# 24LedConnector_1_1.net
KiCad netlist of a schematic drawn in EAGLE
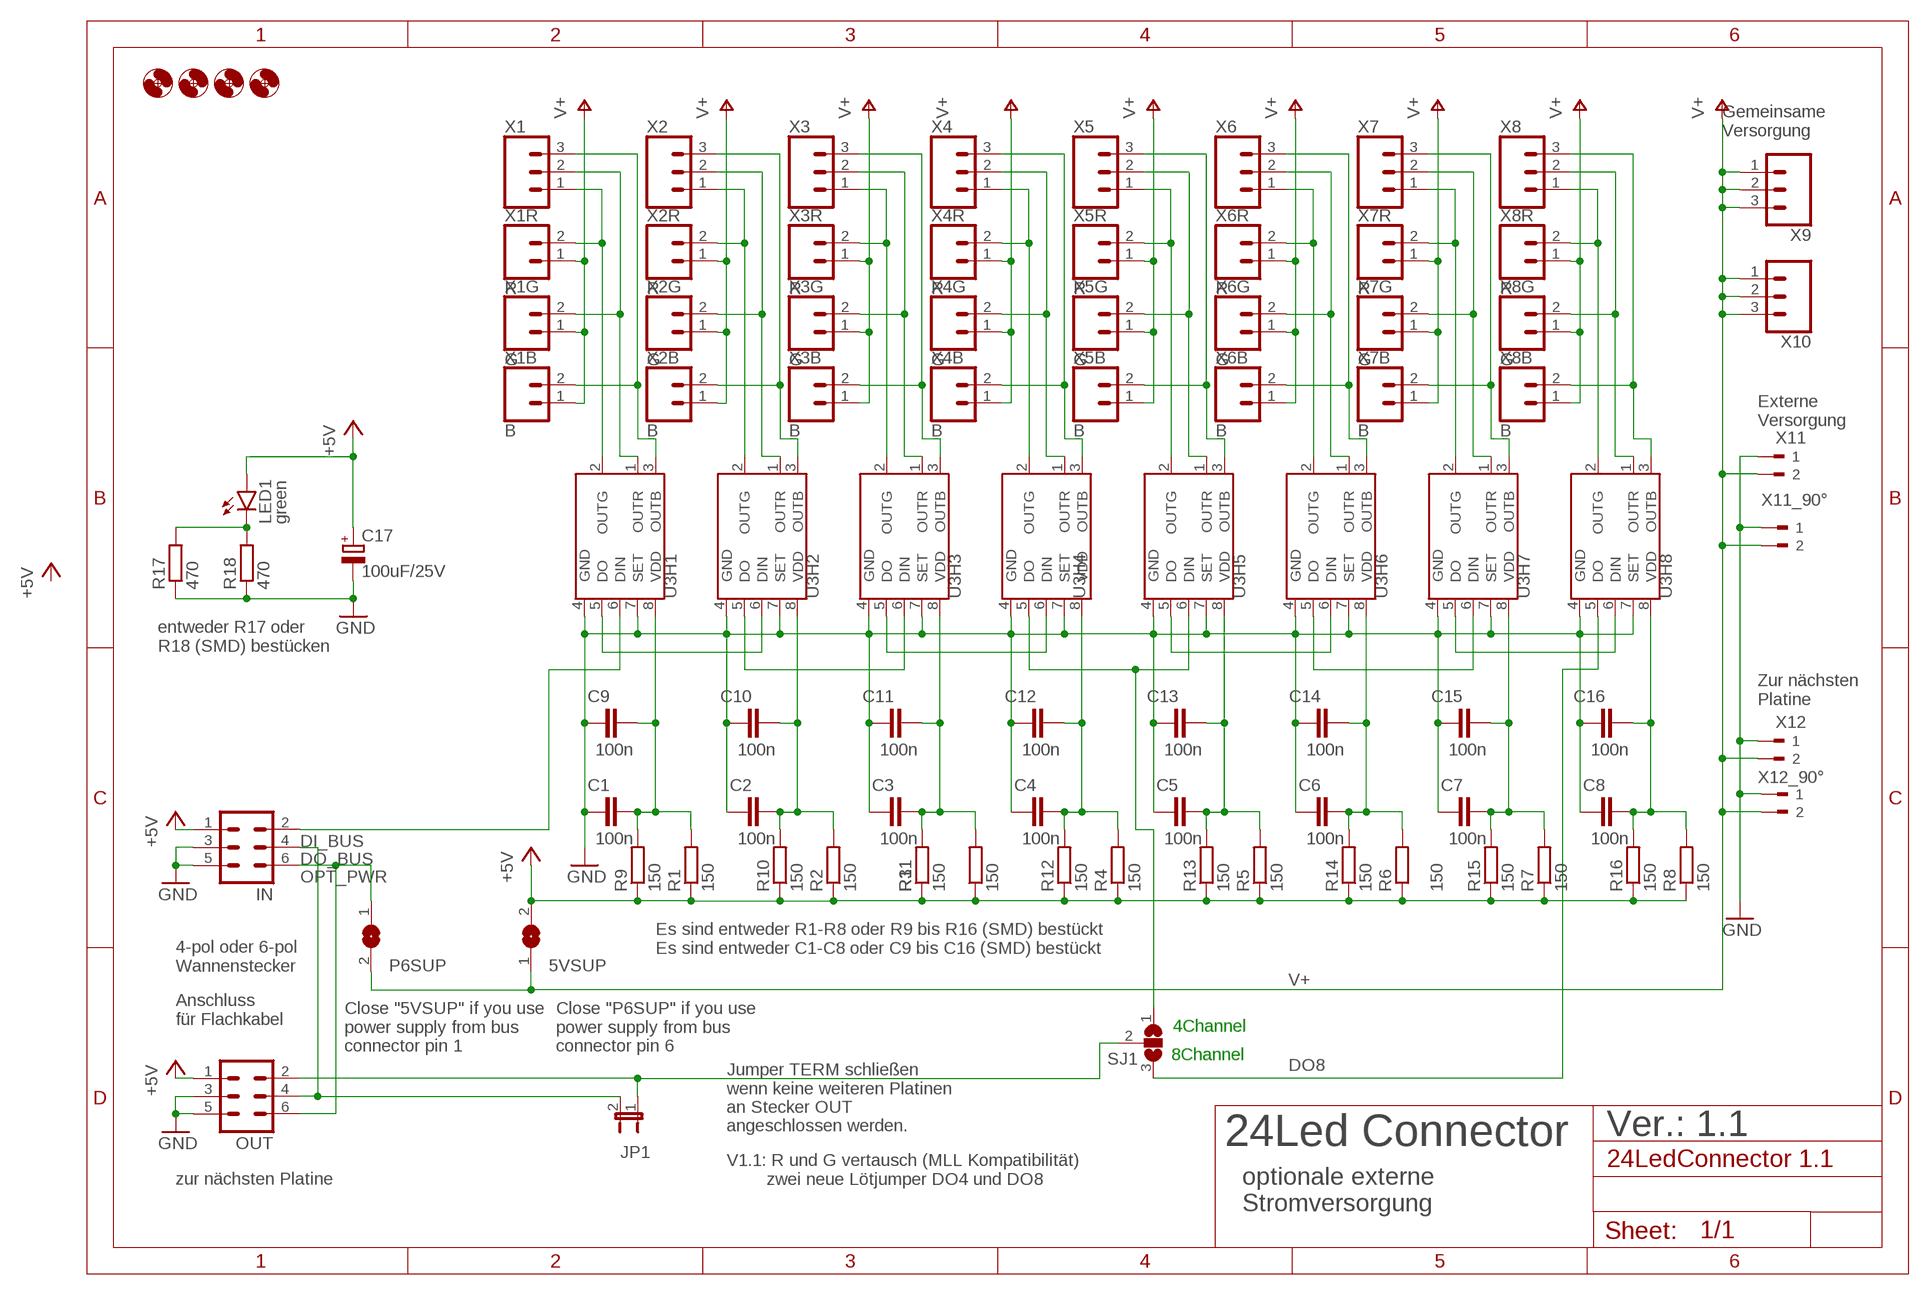
[diagram p0: schematic, sheet 1]

(export (version "E")
  (design (tool "Eeschema 10.0.6"))
  (components
    (comp (ref "5VSUP")
      (value "SJ")
      (footprint "eagle-import:SJ")
      (libsource (lib "eagle-import") (part "SJ"))
    )
    (comp (ref "C1")
      (value "100n")
      (footprint "eagle-import:C025-024X044")
      (libsource (lib "eagle-import") (part "C-EU025-024X044"))
    )
    (comp (ref "C2")
      (value "100n")
      (footprint "eagle-import:C025-024X044")
      (libsource (lib "eagle-import") (part "C-EU025-024X044"))
    )
    (comp (ref "C3")
      (value "100n")
      (footprint "eagle-import:C025-024X044")
      (libsource (lib "eagle-import") (part "C-EU025-024X044"))
    )
    (comp (ref "C4")
      (value "100n")
      (footprint "eagle-import:C025-024X044")
      (libsource (lib "eagle-import") (part "C-EU025-024X044"))
    )
    (comp (ref "C5")
      (value "100n")
      (footprint "eagle-import:C025-024X044")
      (libsource (lib "eagle-import") (part "C-EU025-024X044"))
    )
    (comp (ref "C6")
      (value "100n")
      (footprint "eagle-import:C025-024X044")
      (libsource (lib "eagle-import") (part "C-EU025-024X044"))
    )
    (comp (ref "C7")
      (value "100n")
      (footprint "eagle-import:C025-024X044")
      (libsource (lib "eagle-import") (part "C-EU025-024X044"))
    )
    (comp (ref "C8")
      (value "100n")
      (footprint "eagle-import:C025-024X044")
      (libsource (lib "eagle-import") (part "C-EU025-024X044"))
    )
    (comp (ref "C9")
      (value "100n")
      (footprint "eagle-import:C0805")
      (libsource (lib "eagle-import") (part "C-EUC0805"))
    )
    (comp (ref "C10")
      (value "100n")
      (footprint "eagle-import:C0805")
      (libsource (lib "eagle-import") (part "C-EUC0805"))
    )
    (comp (ref "C11")
      (value "100n")
      (footprint "eagle-import:C0805")
      (libsource (lib "eagle-import") (part "C-EUC0805"))
    )
    (comp (ref "C12")
      (value "100n")
      (footprint "eagle-import:C0805")
      (libsource (lib "eagle-import") (part "C-EUC0805"))
    )
    (comp (ref "C13")
      (value "100n")
      (footprint "eagle-import:C0805")
      (libsource (lib "eagle-import") (part "C-EUC0805"))
    )
    (comp (ref "C14")
      (value "100n")
      (footprint "eagle-import:C0805")
      (libsource (lib "eagle-import") (part "C-EUC0805"))
    )
    (comp (ref "C15")
      (value "100n")
      (footprint "eagle-import:C0805")
      (libsource (lib "eagle-import") (part "C-EUC0805"))
    )
    (comp (ref "C16")
      (value "100n")
      (footprint "eagle-import:C0805")
      (libsource (lib "eagle-import") (part "C-EUC0805"))
    )
    (comp (ref "C17")
      (value "100uF/25V")
      (footprint "eagle-import:E3,5-8")
      (libsource (lib "eagle-import") (part "CPOL-EUE3.5-8"))
    )
    (comp (ref "H1")
      (value "MOUNT-HOLE2.0")
      (footprint "eagle-import:2,0")
      (libsource (lib "eagle-import") (part "MOUNT-HOLE2.0"))
    )
    (comp (ref "H2")
      (value "MOUNT-HOLE2.0")
      (footprint "eagle-import:2,0")
      (libsource (lib "eagle-import") (part "MOUNT-HOLE2.0"))
    )
    (comp (ref "H3")
      (value "MOUNT-HOLE2.0")
      (footprint "eagle-import:2,0")
      (libsource (lib "eagle-import") (part "MOUNT-HOLE2.0"))
    )
    (comp (ref "H4")
      (value "MOUNT-HOLE2.0")
      (footprint "eagle-import:2,0")
      (libsource (lib "eagle-import") (part "MOUNT-HOLE2.0"))
    )
    (comp (ref "IN")
      (value "ML6")
      (footprint "eagle-import:ML6")
      (libsource (lib "eagle-import") (part "ML6"))
    )
    (comp (ref "JP1")
      (value "JP1E")
      (footprint "eagle-import:JP1")
      (libsource (lib "eagle-import") (part "JP1E"))
    )
    (comp (ref "LED1")
      (value "green")
      (footprint "eagle-import:LED3MM")
      (libsource (lib "eagle-import") (part "LED3MM"))
    )
    (comp (ref "OUT")
      (value "ML6")
      (footprint "eagle-import:ML6")
      (libsource (lib "eagle-import") (part "ML6"))
    )
    (comp (ref "P6SUP")
      (value "SJ")
      (footprint "eagle-import:SJ")
      (libsource (lib "eagle-import") (part "SJ"))
    )
    (comp (ref "R1")
      (value "150")
      (footprint "eagle-import:0204V")
      (libsource (lib "eagle-import") (part "R-EU_0204/2V"))
    )
    (comp (ref "R2")
      (value "150")
      (footprint "eagle-import:0204V")
      (libsource (lib "eagle-import") (part "R-EU_0204/2V"))
    )
    (comp (ref "R3")
      (value "150")
      (footprint "eagle-import:0204V")
      (libsource (lib "eagle-import") (part "R-EU_0204/2V"))
    )
    (comp (ref "R4")
      (value "150")
      (footprint "eagle-import:0204V")
      (libsource (lib "eagle-import") (part "R-EU_0204/2V"))
    )
    (comp (ref "R5")
      (value "150")
      (footprint "eagle-import:0204V")
      (libsource (lib "eagle-import") (part "R-EU_0204/2V"))
    )
    (comp (ref "R6")
      (value "150")
      (footprint "eagle-import:0204V")
      (libsource (lib "eagle-import") (part "R-EU_0204/2V"))
    )
    (comp (ref "R7")
      (value "150")
      (footprint "eagle-import:0204V")
      (libsource (lib "eagle-import") (part "R-EU_0204/2V"))
    )
    (comp (ref "R8")
      (value "150")
      (footprint "eagle-import:0204V")
      (libsource (lib "eagle-import") (part "R-EU_0204/2V"))
    )
    (comp (ref "R9")
      (value "150")
      (footprint "eagle-import:M0805")
      (libsource (lib "eagle-import") (part "R-EU_M0805"))
    )
    (comp (ref "R10")
      (value "150")
      (footprint "eagle-import:M0805")
      (libsource (lib "eagle-import") (part "R-EU_M0805"))
    )
    (comp (ref "R11")
      (value "150")
      (footprint "eagle-import:M0805")
      (libsource (lib "eagle-import") (part "R-EU_M0805"))
    )
    (comp (ref "R12")
      (value "150")
      (footprint "eagle-import:M0805")
      (libsource (lib "eagle-import") (part "R-EU_M0805"))
    )
    (comp (ref "R13")
      (value "150")
      (footprint "eagle-import:M0805")
      (libsource (lib "eagle-import") (part "R-EU_M0805"))
    )
    (comp (ref "R14")
      (value "150")
      (footprint "eagle-import:M0805")
      (libsource (lib "eagle-import") (part "R-EU_M0805"))
    )
    (comp (ref "R15")
      (value "150")
      (footprint "eagle-import:M0805")
      (libsource (lib "eagle-import") (part "R-EU_M0805"))
    )
    (comp (ref "R16")
      (value "150")
      (footprint "eagle-import:M0805")
      (libsource (lib "eagle-import") (part "R-EU_M0805"))
    )
    (comp (ref "R17")
      (value "470")
      (footprint "eagle-import:M0805")
      (libsource (lib "eagle-import") (part "R-EU_M0805"))
    )
    (comp (ref "R18")
      (value "470")
      (footprint "eagle-import:0204V")
      (libsource (lib "eagle-import") (part "R-EU_0204/2V"))
    )
    (comp (ref "SJ1")
      (value "SJ2W")
      (footprint "eagle-import:SJ_2")
      (libsource (lib "eagle-import") (part "SJ2W"))
    )
    (comp (ref "U3H1")
      (value "WS2811")
      (footprint "eagle-import:SOP8")
      (libsource (lib "eagle-import") (part "S3PO_MODUL_WS2811_SOUND_MP3-TF-16P_WS2811_AND_ATTINY_WS2811-ICSOP8"))
    )
    (comp (ref "U3H2")
      (value "WS2811")
      (footprint "eagle-import:SOP8")
      (libsource (lib "eagle-import") (part "S3PO_MODUL_WS2811_SOUND_MP3-TF-16P_WS2811_AND_ATTINY_WS2811-ICSOP8"))
    )
    (comp (ref "U3H3")
      (value "WS2811")
      (footprint "eagle-import:SOP8")
      (libsource (lib "eagle-import") (part "S3PO_MODUL_WS2811_SOUND_MP3-TF-16P_WS2811_AND_ATTINY_WS2811-ICSOP8"))
    )
    (comp (ref "U3H4")
      (value "WS2811")
      (footprint "eagle-import:SOP8")
      (libsource (lib "eagle-import") (part "S3PO_MODUL_WS2811_SOUND_MP3-TF-16P_WS2811_AND_ATTINY_WS2811-ICSOP8"))
    )
    (comp (ref "U3H5")
      (value "WS2811")
      (footprint "eagle-import:SOP8")
      (libsource (lib "eagle-import") (part "S3PO_MODUL_WS2811_SOUND_MP3-TF-16P_WS2811_AND_ATTINY_WS2811-ICSOP8"))
    )
    (comp (ref "U3H6")
      (value "WS2811")
      (footprint "eagle-import:SOP8")
      (libsource (lib "eagle-import") (part "S3PO_MODUL_WS2811_SOUND_MP3-TF-16P_WS2811_AND_ATTINY_WS2811-ICSOP8"))
    )
    (comp (ref "U3H7")
      (value "WS2811")
      (footprint "eagle-import:SOP8")
      (libsource (lib "eagle-import") (part "S3PO_MODUL_WS2811_SOUND_MP3-TF-16P_WS2811_AND_ATTINY_WS2811-ICSOP8"))
    )
    (comp (ref "U3H8")
      (value "WS2811")
      (footprint "eagle-import:SOP8")
      (libsource (lib "eagle-import") (part "S3PO_MODUL_WS2811_SOUND_MP3-TF-16P_WS2811_AND_ATTINY_WS2811-ICSOP8"))
    )
    (comp (ref "X1")
      (value "CONN_03SCREW-NS")
      (footprint "eagle-import:SCREWTERMINAL-3.5MM-3-NS")
      (libsource (lib "eagle-import") (part "CONN_03SCREW-NS"))
    )
    (comp (ref "X1B")
      (value "B")
      (footprint "eagle-import:1X02")
      (libsource (lib "eagle-import") (part "CONN_02"))
    )
    (comp (ref "X1G")
      (value "G")
      (footprint "eagle-import:1X02")
      (libsource (lib "eagle-import") (part "CONN_02"))
    )
    (comp (ref "X1R")
      (value "R")
      (footprint "eagle-import:1X02")
      (libsource (lib "eagle-import") (part "CONN_02"))
    )
    (comp (ref "X2")
      (value "CONN_03SCREW-NS")
      (footprint "eagle-import:SCREWTERMINAL-3.5MM-3-NS")
      (libsource (lib "eagle-import") (part "CONN_03SCREW-NS"))
    )
    (comp (ref "X2B")
      (value "B")
      (footprint "eagle-import:1X02")
      (libsource (lib "eagle-import") (part "CONN_02"))
    )
    (comp (ref "X2G")
      (value "G")
      (footprint "eagle-import:1X02")
      (libsource (lib "eagle-import") (part "CONN_02"))
    )
    (comp (ref "X2R")
      (value "R")
      (footprint "eagle-import:1X02")
      (libsource (lib "eagle-import") (part "CONN_02"))
    )
    (comp (ref "X3")
      (value "CONN_03SCREW-NS")
      (footprint "eagle-import:SCREWTERMINAL-3.5MM-3-NS")
      (libsource (lib "eagle-import") (part "CONN_03SCREW-NS"))
    )
    (comp (ref "X3B")
      (value "B")
      (footprint "eagle-import:1X02")
      (libsource (lib "eagle-import") (part "CONN_02"))
    )
    (comp (ref "X3G")
      (value "G")
      (footprint "eagle-import:1X02")
      (libsource (lib "eagle-import") (part "CONN_02"))
    )
    (comp (ref "X3R")
      (value "R")
      (footprint "eagle-import:1X02")
      (libsource (lib "eagle-import") (part "CONN_02"))
    )
    (comp (ref "X4")
      (value "CONN_03SCREW-NS")
      (footprint "eagle-import:SCREWTERMINAL-3.5MM-3-NS")
      (libsource (lib "eagle-import") (part "CONN_03SCREW-NS"))
    )
    (comp (ref "X4B")
      (value "B")
      (footprint "eagle-import:1X02")
      (libsource (lib "eagle-import") (part "CONN_02"))
    )
    (comp (ref "X4G")
      (value "G")
      (footprint "eagle-import:1X02")
      (libsource (lib "eagle-import") (part "CONN_02"))
    )
    (comp (ref "X4R")
      (value "R")
      (footprint "eagle-import:1X02")
      (libsource (lib "eagle-import") (part "CONN_02"))
    )
    (comp (ref "X5")
      (value "CONN_03SCREW-NS")
      (footprint "eagle-import:SCREWTERMINAL-3.5MM-3-NS")
      (libsource (lib "eagle-import") (part "CONN_03SCREW-NS"))
    )
    (comp (ref "X5B")
      (value "B")
      (footprint "eagle-import:1X02")
      (libsource (lib "eagle-import") (part "CONN_02"))
    )
    (comp (ref "X5G")
      (value "G")
      (footprint "eagle-import:1X02")
      (libsource (lib "eagle-import") (part "CONN_02"))
    )
    (comp (ref "X5R")
      (value "R")
      (footprint "eagle-import:1X02")
      (libsource (lib "eagle-import") (part "CONN_02"))
    )
    (comp (ref "X6")
      (value "CONN_03SCREW-NS")
      (footprint "eagle-import:SCREWTERMINAL-3.5MM-3-NS")
      (libsource (lib "eagle-import") (part "CONN_03SCREW-NS"))
    )
    (comp (ref "X6B")
      (value "B")
      (footprint "eagle-import:1X02")
      (libsource (lib "eagle-import") (part "CONN_02"))
    )
    (comp (ref "X6G")
      (value "G")
      (footprint "eagle-import:1X02")
      (libsource (lib "eagle-import") (part "CONN_02"))
    )
    (comp (ref "X6R")
      (value "R")
      (footprint "eagle-import:1X02")
      (libsource (lib "eagle-import") (part "CONN_02"))
    )
    (comp (ref "X7")
      (value "CONN_03SCREW-NS")
      (footprint "eagle-import:SCREWTERMINAL-3.5MM-3-NS")
      (libsource (lib "eagle-import") (part "CONN_03SCREW-NS"))
    )
    (comp (ref "X7B")
      (value "B")
      (footprint "eagle-import:1X02")
      (libsource (lib "eagle-import") (part "CONN_02"))
    )
    (comp (ref "X7G")
      (value "G")
      (footprint "eagle-import:1X02")
      (libsource (lib "eagle-import") (part "CONN_02"))
    )
    (comp (ref "X7R")
      (value "R")
      (footprint "eagle-import:1X02")
      (libsource (lib "eagle-import") (part "CONN_02"))
    )
    (comp (ref "X8")
      (value "CONN_03SCREW-NS")
      (footprint "eagle-import:SCREWTERMINAL-3.5MM-3-NS")
      (libsource (lib "eagle-import") (part "CONN_03SCREW-NS"))
    )
    (comp (ref "X8B")
      (value "B")
      (footprint "eagle-import:1X02")
      (libsource (lib "eagle-import") (part "CONN_02"))
    )
    (comp (ref "X8G")
      (value "G")
      (footprint "eagle-import:1X02")
      (libsource (lib "eagle-import") (part "CONN_02"))
    )
    (comp (ref "X8R")
      (value "R")
      (footprint "eagle-import:1X02")
      (libsource (lib "eagle-import") (part "CONN_02"))
    )
    (comp (ref "X9")
      (value "CONN_03SCREW-NS")
      (footprint "eagle-import:SCREWTERMINAL-3.5MM-3-NS")
      (libsource (lib "eagle-import") (part "CONN_03SCREW-NS"))
    )
    (comp (ref "X10")
      (value "CONN_03SCREW-NS")
      (footprint "eagle-import:SCREWTERMINAL-3.5MM-3-NS")
      (libsource (lib "eagle-import") (part "CONN_03SCREW-NS"))
    )
    (comp (ref "X11")
      (value "180-2")
      (footprint "eagle-import:180-2")
      (libsource (lib "eagle-import") (part "180-2"))
    )
    (comp (ref "X11_90°")
      (value "90-2")
      (footprint "eagle-import:90-2")
      (libsource (lib "eagle-import") (part "90-2"))
    )
    (comp (ref "X12")
      (value "180-2")
      (footprint "eagle-import:180-2")
      (libsource (lib "eagle-import") (part "180-2"))
    )
    (comp (ref "X12_90°")
      (value "90-2")
      (footprint "eagle-import:90-2")
      (libsource (lib "eagle-import") (part "90-2"))
    )
  )
  (nets
    (net (code "1") (name "+5V") (class "Default")
      (node (ref "5VSUP") (pin "2") (pinfunction "2_2") (pintype "passive"))
      (node (ref "C17") (pin "+") (pinfunction "+_+") (pintype "passive"))
      (node (ref "IN") (pin "1") (pinfunction "1_1") (pintype "passive"))
      (node (ref "LED1") (pin "A") (pinfunction "A_A") (pintype "passive"))
      (node (ref "OUT") (pin "1") (pinfunction "1_1") (pintype "passive"))
      (node (ref "R1") (pin "1") (pinfunction "1_1") (pintype "passive"))
      (node (ref "R10") (pin "1") (pinfunction "1_1") (pintype "passive"))
      (node (ref "R11") (pin "1") (pinfunction "1_1") (pintype "passive"))
      (node (ref "R12") (pin "1") (pinfunction "1_1") (pintype "passive"))
      (node (ref "R13") (pin "1") (pinfunction "1_1") (pintype "passive"))
      (node (ref "R14") (pin "1") (pinfunction "1_1") (pintype "passive"))
      (node (ref "R15") (pin "1") (pinfunction "1_1") (pintype "passive"))
      (node (ref "R16") (pin "1") (pinfunction "1_1") (pintype "passive"))
      (node (ref "R2") (pin "1") (pinfunction "1_1") (pintype "passive"))
      (node (ref "R3") (pin "1") (pinfunction "1_1") (pintype "passive"))
      (node (ref "R4") (pin "1") (pinfunction "1_1") (pintype "passive"))
      (node (ref "R5") (pin "1") (pinfunction "1_1") (pintype "passive"))
      (node (ref "R6") (pin "1") (pinfunction "1_1") (pintype "passive"))
      (node (ref "R7") (pin "1") (pinfunction "1_1") (pintype "passive"))
      (node (ref "R8") (pin "1") (pinfunction "1_1") (pintype "passive"))
      (node (ref "R9") (pin "1") (pinfunction "1_1") (pintype "passive"))
    )
    (net (code "2") (name "/DI_BUS") (class "Default")
      (node (ref "IN") (pin "2") (pinfunction "2_2") (pintype "passive"))
      (node (ref "U3H1") (pin "6") (pinfunction "DIN_6") (pintype "input"))
    )
    (net (code "3") (name "/DO8") (class "Default")
      (node (ref "SJ1") (pin "3") (pinfunction "3_3") (pintype "passive"))
      (node (ref "U3H8") (pin "5") (pinfunction "DO_5") (pintype "output"))
    )
    (net (code "4") (name "/DO_BUS") (class "Default")
      (node (ref "IN") (pin "4") (pinfunction "4_4") (pintype "passive"))
      (node (ref "JP1") (pin "2") (pinfunction "2_2") (pintype "passive"))
      (node (ref "OUT") (pin "4") (pinfunction "4_4") (pintype "passive"))
    )
    (net (code "5") (name "/OPT_PWR") (class "Default")
      (node (ref "IN") (pin "6") (pinfunction "6_6") (pintype "passive"))
      (node (ref "OUT") (pin "6") (pinfunction "6_6") (pintype "passive"))
      (node (ref "P6SUP") (pin "1") (pinfunction "1_1") (pintype "passive"))
    )
    (net (code "6") (name "GND") (class "Default")
      (node (ref "C1") (pin "1") (pinfunction "1_1") (pintype "passive"))
      (node (ref "C10") (pin "1") (pinfunction "1_1") (pintype "passive"))
      (node (ref "C11") (pin "1") (pinfunction "1_1") (pintype "passive"))
      (node (ref "C12") (pin "1") (pinfunction "1_1") (pintype "passive"))
      (node (ref "C13") (pin "1") (pinfunction "1_1") (pintype "passive"))
      (node (ref "C14") (pin "1") (pinfunction "1_1") (pintype "passive"))
      (node (ref "C15") (pin "1") (pinfunction "1_1") (pintype "passive"))
      (node (ref "C16") (pin "1") (pinfunction "1_1") (pintype "passive"))
      (node (ref "C17") (pin "-") (pinfunction "-_-") (pintype "passive"))
      (node (ref "C2") (pin "1") (pinfunction "1_1") (pintype "passive"))
      (node (ref "C3") (pin "1") (pinfunction "1_1") (pintype "passive"))
      (node (ref "C4") (pin "1") (pinfunction "1_1") (pintype "passive"))
      (node (ref "C5") (pin "1") (pinfunction "1_1") (pintype "passive"))
      (node (ref "C6") (pin "1") (pinfunction "1_1") (pintype "passive"))
      (node (ref "C7") (pin "1") (pinfunction "1_1") (pintype "passive"))
      (node (ref "C8") (pin "1") (pinfunction "1_1") (pintype "passive"))
      (node (ref "C9") (pin "1") (pinfunction "1_1") (pintype "passive"))
      (node (ref "IN") (pin "3") (pinfunction "3_3") (pintype "passive"))
      (node (ref "IN") (pin "5") (pinfunction "5_5") (pintype "passive"))
      (node (ref "OUT") (pin "3") (pinfunction "3_3") (pintype "passive"))
      (node (ref "OUT") (pin "5") (pinfunction "5_5") (pintype "passive"))
      (node (ref "R17") (pin "1") (pinfunction "1_1") (pintype "passive"))
      (node (ref "R18") (pin "1") (pinfunction "1_1") (pintype "passive"))
      (node (ref "U3H1") (pin "4") (pinfunction "GND_4") (pintype "power_in"))
      (node (ref "U3H1") (pin "7") (pinfunction "SET_7") (pintype "bidirectional"))
      (node (ref "U3H2") (pin "4") (pinfunction "GND_4") (pintype "power_in"))
      (node (ref "U3H2") (pin "7") (pinfunction "SET_7") (pintype "bidirectional"))
      (node (ref "U3H3") (pin "4") (pinfunction "GND_4") (pintype "power_in"))
      (node (ref "U3H3") (pin "7") (pinfunction "SET_7") (pintype "bidirectional"))
      (node (ref "U3H4") (pin "4") (pinfunction "GND_4") (pintype "power_in"))
      (node (ref "U3H4") (pin "7") (pinfunction "SET_7") (pintype "bidirectional"))
      (node (ref "U3H5") (pin "4") (pinfunction "GND_4") (pintype "power_in"))
      (node (ref "U3H5") (pin "7") (pinfunction "SET_7") (pintype "bidirectional"))
      (node (ref "U3H6") (pin "4") (pinfunction "GND_4") (pintype "power_in"))
      (node (ref "U3H6") (pin "7") (pinfunction "SET_7") (pintype "bidirectional"))
      (node (ref "U3H7") (pin "4") (pinfunction "GND_4") (pintype "power_in"))
      (node (ref "U3H7") (pin "7") (pinfunction "SET_7") (pintype "bidirectional"))
      (node (ref "U3H8") (pin "4") (pinfunction "GND_4") (pintype "power_in"))
      (node (ref "U3H8") (pin "7") (pinfunction "SET_7") (pintype "bidirectional"))
      (node (ref "X11") (pin "1") (pinfunction "1_1") (pintype "passive"))
      (node (ref "X11_90°") (pin "1") (pinfunction "1_1") (pintype "passive"))
      (node (ref "X12") (pin "1") (pinfunction "1_1") (pintype "passive"))
      (node (ref "X12_90°") (pin "1") (pinfunction "1_1") (pintype "passive"))
    )
    (net (code "7") (name "Net-(JP1-Pad1)") (class "Default")
      (node (ref "JP1") (pin "1") (pinfunction "1_1") (pintype "passive"))
      (node (ref "OUT") (pin "2") (pinfunction "2_2") (pintype "passive"))
      (node (ref "SJ1") (pin "2") (pinfunction "2_2") (pintype "passive"))
    )
    (net (code "8") (name "Net-(LED1-C)") (class "Default")
      (node (ref "LED1") (pin "K") (pinfunction "C_K") (pintype "passive"))
      (node (ref "R17") (pin "2") (pinfunction "2_2") (pintype "passive"))
      (node (ref "R18") (pin "2") (pinfunction "2_2") (pintype "passive"))
    )
    (net (code "9") (name "Net-(U3H1-DO)") (class "Default")
      (node (ref "U3H1") (pin "5") (pinfunction "DO_5") (pintype "output"))
      (node (ref "U3H2") (pin "6") (pinfunction "DIN_6") (pintype "input"))
    )
    (net (code "10") (name "Net-(U3H1-OUTB)") (class "Default")
      (node (ref "U3H1") (pin "3") (pinfunction "OUTB_3") (pintype "open_collector"))
      (node (ref "X1") (pin "3") (pinfunction "3_3") (pintype "passive"))
      (node (ref "X1B") (pin "2") (pinfunction "2_2") (pintype "passive"))
    )
    (net (code "11") (name "Net-(U3H1-OUTG)") (class "Default")
      (node (ref "U3H1") (pin "2") (pinfunction "OUTG_2") (pintype "open_collector"))
      (node (ref "X1") (pin "1") (pinfunction "1_1") (pintype "passive"))
      (node (ref "X1R") (pin "2") (pinfunction "2_2") (pintype "passive"))
    )
    (net (code "12") (name "Net-(U3H1-OUTR)") (class "Default")
      (node (ref "U3H1") (pin "1") (pinfunction "OUTR_1") (pintype "open_collector"))
      (node (ref "X1") (pin "2") (pinfunction "2_2") (pintype "passive"))
      (node (ref "X1G") (pin "2") (pinfunction "2_2") (pintype "passive"))
    )
    (net (code "13") (name "Net-(U3H1-VDD)") (class "Default")
      (node (ref "C1") (pin "2") (pinfunction "2_2") (pintype "passive"))
      (node (ref "C9") (pin "2") (pinfunction "2_2") (pintype "passive"))
      (node (ref "R1") (pin "2") (pinfunction "2_2") (pintype "passive"))
      (node (ref "R9") (pin "2") (pinfunction "2_2") (pintype "passive"))
      (node (ref "U3H1") (pin "8") (pinfunction "VDD_8") (pintype "power_in"))
    )
    (net (code "14") (name "Net-(U3H2-DO)") (class "Default")
      (node (ref "U3H2") (pin "5") (pinfunction "DO_5") (pintype "output"))
      (node (ref "U3H3") (pin "6") (pinfunction "DIN_6") (pintype "input"))
    )
    (net (code "15") (name "Net-(U3H2-OUTB)") (class "Default")
      (node (ref "U3H2") (pin "3") (pinfunction "OUTB_3") (pintype "open_collector"))
      (node (ref "X2") (pin "3") (pinfunction "3_3") (pintype "passive"))
      (node (ref "X2B") (pin "2") (pinfunction "2_2") (pintype "passive"))
    )
    (net (code "16") (name "Net-(U3H2-OUTG)") (class "Default")
      (node (ref "U3H2") (pin "2") (pinfunction "OUTG_2") (pintype "open_collector"))
      (node (ref "X2") (pin "1") (pinfunction "1_1") (pintype "passive"))
      (node (ref "X2R") (pin "2") (pinfunction "2_2") (pintype "passive"))
    )
    (net (code "17") (name "Net-(U3H2-OUTR)") (class "Default")
      (node (ref "U3H2") (pin "1") (pinfunction "OUTR_1") (pintype "open_collector"))
      (node (ref "X2") (pin "2") (pinfunction "2_2") (pintype "passive"))
      (node (ref "X2G") (pin "2") (pinfunction "2_2") (pintype "passive"))
    )
    (net (code "18") (name "Net-(U3H2-VDD)") (class "Default")
      (node (ref "C10") (pin "2") (pinfunction "2_2") (pintype "passive"))
      (node (ref "C2") (pin "2") (pinfunction "2_2") (pintype "passive"))
      (node (ref "R10") (pin "2") (pinfunction "2_2") (pintype "passive"))
      (node (ref "R2") (pin "2") (pinfunction "2_2") (pintype "passive"))
      (node (ref "U3H2") (pin "8") (pinfunction "VDD_8") (pintype "power_in"))
    )
    (net (code "19") (name "Net-(U3H3-DO)") (class "Default")
      (node (ref "U3H3") (pin "5") (pinfunction "DO_5") (pintype "output"))
      (node (ref "U3H4") (pin "6") (pinfunction "DIN_6") (pintype "input"))
    )
    (net (code "20") (name "Net-(U3H3-OUTB)") (class "Default")
      (node (ref "U3H3") (pin "3") (pinfunction "OUTB_3") (pintype "open_collector"))
      (node (ref "X3") (pin "3") (pinfunction "3_3") (pintype "passive"))
      (node (ref "X3B") (pin "2") (pinfunction "2_2") (pintype "passive"))
    )
    (net (code "21") (name "Net-(U3H3-OUTG)") (class "Default")
      (node (ref "U3H3") (pin "2") (pinfunction "OUTG_2") (pintype "open_collector"))
      (node (ref "X3") (pin "1") (pinfunction "1_1") (pintype "passive"))
      (node (ref "X3R") (pin "2") (pinfunction "2_2") (pintype "passive"))
    )
    (net (code "22") (name "Net-(U3H3-OUTR)") (class "Default")
      (node (ref "U3H3") (pin "1") (pinfunction "OUTR_1") (pintype "open_collector"))
      (node (ref "X3") (pin "2") (pinfunction "2_2") (pintype "passive"))
      (node (ref "X3G") (pin "2") (pinfunction "2_2") (pintype "passive"))
    )
    (net (code "23") (name "Net-(U3H3-VDD)") (class "Default")
      (node (ref "C11") (pin "2") (pinfunction "2_2") (pintype "passive"))
      (node (ref "C3") (pin "2") (pinfunction "2_2") (pintype "passive"))
      (node (ref "R11") (pin "2") (pinfunction "2_2") (pintype "passive"))
      (node (ref "R3") (pin "2") (pinfunction "2_2") (pintype "passive"))
      (node (ref "U3H3") (pin "8") (pinfunction "VDD_8") (pintype "power_in"))
    )
    (net (code "24") (name "Net-(U3H4-DO)") (class "Default")
      (node (ref "SJ1") (pin "1") (pinfunction "1_1") (pintype "passive"))
      (node (ref "U3H4") (pin "5") (pinfunction "DO_5") (pintype "output"))
      (node (ref "U3H5") (pin "6") (pinfunction "DIN_6") (pintype "input"))
    )
    (net (code "25") (name "Net-(U3H4-OUTB)") (class "Default")
      (node (ref "U3H4") (pin "3") (pinfunction "OUTB_3") (pintype "open_collector"))
      (node (ref "X4") (pin "3") (pinfunction "3_3") (pintype "passive"))
      (node (ref "X4B") (pin "2") (pinfunction "2_2") (pintype "passive"))
    )
    (net (code "26") (name "Net-(U3H4-OUTG)") (class "Default")
      (node (ref "U3H4") (pin "2") (pinfunction "OUTG_2") (pintype "open_collector"))
      (node (ref "X4") (pin "1") (pinfunction "1_1") (pintype "passive"))
      (node (ref "X4R") (pin "2") (pinfunction "2_2") (pintype "passive"))
    )
    (net (code "27") (name "Net-(U3H4-OUTR)") (class "Default")
      (node (ref "U3H4") (pin "1") (pinfunction "OUTR_1") (pintype "open_collector"))
      (node (ref "X4") (pin "2") (pinfunction "2_2") (pintype "passive"))
      (node (ref "X4G") (pin "2") (pinfunction "2_2") (pintype "passive"))
    )
    (net (code "28") (name "Net-(U3H4-VDD)") (class "Default")
      (node (ref "C12") (pin "2") (pinfunction "2_2") (pintype "passive"))
      (node (ref "C4") (pin "2") (pinfunction "2_2") (pintype "passive"))
      (node (ref "R12") (pin "2") (pinfunction "2_2") (pintype "passive"))
      (node (ref "R4") (pin "2") (pinfunction "2_2") (pintype "passive"))
      (node (ref "U3H4") (pin "8") (pinfunction "VDD_8") (pintype "power_in"))
    )
    (net (code "29") (name "Net-(U3H5-DO)") (class "Default")
      (node (ref "U3H5") (pin "5") (pinfunction "DO_5") (pintype "output"))
      (node (ref "U3H6") (pin "6") (pinfunction "DIN_6") (pintype "input"))
    )
    (net (code "30") (name "Net-(U3H5-OUTB)") (class "Default")
      (node (ref "U3H5") (pin "3") (pinfunction "OUTB_3") (pintype "open_collector"))
      (node (ref "X5") (pin "3") (pinfunction "3_3") (pintype "passive"))
      (node (ref "X5B") (pin "2") (pinfunction "2_2") (pintype "passive"))
    )
    (net (code "31") (name "Net-(U3H5-OUTG)") (class "Default")
      (node (ref "U3H5") (pin "2") (pinfunction "OUTG_2") (pintype "open_collector"))
      (node (ref "X5") (pin "1") (pinfunction "1_1") (pintype "passive"))
      (node (ref "X5R") (pin "2") (pinfunction "2_2") (pintype "passive"))
    )
    (net (code "32") (name "Net-(U3H5-OUTR)") (class "Default")
      (node (ref "U3H5") (pin "1") (pinfunction "OUTR_1") (pintype "open_collector"))
      (node (ref "X5") (pin "2") (pinfunction "2_2") (pintype "passive"))
      (node (ref "X5G") (pin "2") (pinfunction "2_2") (pintype "passive"))
    )
    (net (code "33") (name "Net-(U3H5-VDD)") (class "Default")
      (node (ref "C13") (pin "2") (pinfunction "2_2") (pintype "passive"))
      (node (ref "C5") (pin "2") (pinfunction "2_2") (pintype "passive"))
      (node (ref "R13") (pin "2") (pinfunction "2_2") (pintype "passive"))
      (node (ref "R5") (pin "2") (pinfunction "2_2") (pintype "passive"))
      (node (ref "U3H5") (pin "8") (pinfunction "VDD_8") (pintype "power_in"))
    )
    (net (code "34") (name "Net-(U3H6-DO)") (class "Default")
      (node (ref "U3H6") (pin "5") (pinfunction "DO_5") (pintype "output"))
      (node (ref "U3H7") (pin "6") (pinfunction "DIN_6") (pintype "input"))
    )
    (net (code "35") (name "Net-(U3H6-OUTB)") (class "Default")
      (node (ref "U3H6") (pin "3") (pinfunction "OUTB_3") (pintype "open_collector"))
      (node (ref "X6") (pin "3") (pinfunction "3_3") (pintype "passive"))
      (node (ref "X6B") (pin "2") (pinfunction "2_2") (pintype "passive"))
    )
    (net (code "36") (name "Net-(U3H6-OUTG)") (class "Default")
      (node (ref "U3H6") (pin "2") (pinfunction "OUTG_2") (pintype "open_collector"))
      (node (ref "X6") (pin "1") (pinfunction "1_1") (pintype "passive"))
      (node (ref "X6R") (pin "2") (pinfunction "2_2") (pintype "passive"))
    )
    (net (code "37") (name "Net-(U3H6-OUTR)") (class "Default")
      (node (ref "U3H6") (pin "1") (pinfunction "OUTR_1") (pintype "open_collector"))
      (node (ref "X6") (pin "2") (pinfunction "2_2") (pintype "passive"))
      (node (ref "X6G") (pin "2") (pinfunction "2_2") (pintype "passive"))
    )
    (net (code "38") (name "Net-(U3H6-VDD)") (class "Default")
      (node (ref "C14") (pin "2") (pinfunction "2_2") (pintype "passive"))
      (node (ref "C6") (pin "2") (pinfunction "2_2") (pintype "passive"))
      (node (ref "R14") (pin "2") (pinfunction "2_2") (pintype "passive"))
      (node (ref "R6") (pin "2") (pinfunction "2_2") (pintype "passive"))
      (node (ref "U3H6") (pin "8") (pinfunction "VDD_8") (pintype "power_in"))
    )
    (net (code "39") (name "Net-(U3H7-DO)") (class "Default")
      (node (ref "U3H7") (pin "5") (pinfunction "DO_5") (pintype "output"))
      (node (ref "U3H8") (pin "6") (pinfunction "DIN_6") (pintype "input"))
    )
    (net (code "40") (name "Net-(U3H7-OUTB)") (class "Default")
      (node (ref "U3H7") (pin "3") (pinfunction "OUTB_3") (pintype "open_collector"))
      (node (ref "X7") (pin "3") (pinfunction "3_3") (pintype "passive"))
      (node (ref "X7B") (pin "2") (pinfunction "2_2") (pintype "passive"))
    )
    (net (code "41") (name "Net-(U3H7-OUTG)") (class "Default")
      (node (ref "U3H7") (pin "2") (pinfunction "OUTG_2") (pintype "open_collector"))
      (node (ref "X7") (pin "1") (pinfunction "1_1") (pintype "passive"))
      (node (ref "X7R") (pin "2") (pinfunction "2_2") (pintype "passive"))
    )
    (net (code "42") (name "Net-(U3H7-OUTR)") (class "Default")
      (node (ref "U3H7") (pin "1") (pinfunction "OUTR_1") (pintype "open_collector"))
      (node (ref "X7") (pin "2") (pinfunction "2_2") (pintype "passive"))
      (node (ref "X7G") (pin "2") (pinfunction "2_2") (pintype "passive"))
    )
    (net (code "43") (name "Net-(U3H7-VDD)") (class "Default")
      (node (ref "C15") (pin "2") (pinfunction "2_2") (pintype "passive"))
      (node (ref "C7") (pin "2") (pinfunction "2_2") (pintype "passive"))
      (node (ref "R15") (pin "2") (pinfunction "2_2") (pintype "passive"))
      (node (ref "R7") (pin "2") (pinfunction "2_2") (pintype "passive"))
      (node (ref "U3H7") (pin "8") (pinfunction "VDD_8") (pintype "power_in"))
    )
    (net (code "44") (name "Net-(U3H8-OUTB)") (class "Default")
      (node (ref "U3H8") (pin "3") (pinfunction "OUTB_3") (pintype "open_collector"))
      (node (ref "X8") (pin "3") (pinfunction "3_3") (pintype "passive"))
      (node (ref "X8B") (pin "2") (pinfunction "2_2") (pintype "passive"))
    )
    (net (code "45") (name "Net-(U3H8-OUTG)") (class "Default")
      (node (ref "U3H8") (pin "2") (pinfunction "OUTG_2") (pintype "open_collector"))
      (node (ref "X8") (pin "1") (pinfunction "1_1") (pintype "passive"))
      (node (ref "X8R") (pin "2") (pinfunction "2_2") (pintype "passive"))
    )
    (net (code "46") (name "Net-(U3H8-OUTR)") (class "Default")
      (node (ref "U3H8") (pin "1") (pinfunction "OUTR_1") (pintype "open_collector"))
      (node (ref "X8") (pin "2") (pinfunction "2_2") (pintype "passive"))
      (node (ref "X8G") (pin "2") (pinfunction "2_2") (pintype "passive"))
    )
    (net (code "47") (name "Net-(U3H8-VDD)") (class "Default")
      (node (ref "C16") (pin "2") (pinfunction "2_2") (pintype "passive"))
      (node (ref "C8") (pin "2") (pinfunction "2_2") (pintype "passive"))
      (node (ref "R16") (pin "2") (pinfunction "2_2") (pintype "passive"))
      (node (ref "R8") (pin "2") (pinfunction "2_2") (pintype "passive"))
      (node (ref "U3H8") (pin "8") (pinfunction "VDD_8") (pintype "power_in"))
    )
    (net (code "48") (name "V+") (class "Default")
      (node (ref "5VSUP") (pin "1") (pinfunction "1_1") (pintype "passive"))
      (node (ref "P6SUP") (pin "2") (pinfunction "2_2") (pintype "passive"))
      (node (ref "X10") (pin "1") (pinfunction "1_1") (pintype "passive"))
      (node (ref "X10") (pin "2") (pinfunction "2_2") (pintype "passive"))
      (node (ref "X10") (pin "3") (pinfunction "3_3") (pintype "passive"))
      (node (ref "X11") (pin "2") (pinfunction "2_2") (pintype "passive"))
      (node (ref "X11_90°") (pin "2") (pinfunction "2_2") (pintype "passive"))
      (node (ref "X12") (pin "2") (pinfunction "2_2") (pintype "passive"))
      (node (ref "X12_90°") (pin "2") (pinfunction "2_2") (pintype "passive"))
      (node (ref "X1B") (pin "1") (pinfunction "1_1") (pintype "passive"))
      (node (ref "X1G") (pin "1") (pinfunction "1_1") (pintype "passive"))
      (node (ref "X1R") (pin "1") (pinfunction "1_1") (pintype "passive"))
      (node (ref "X2B") (pin "1") (pinfunction "1_1") (pintype "passive"))
      (node (ref "X2G") (pin "1") (pinfunction "1_1") (pintype "passive"))
      (node (ref "X2R") (pin "1") (pinfunction "1_1") (pintype "passive"))
      (node (ref "X3B") (pin "1") (pinfunction "1_1") (pintype "passive"))
      (node (ref "X3G") (pin "1") (pinfunction "1_1") (pintype "passive"))
      (node (ref "X3R") (pin "1") (pinfunction "1_1") (pintype "passive"))
      (node (ref "X4B") (pin "1") (pinfunction "1_1") (pintype "passive"))
      (node (ref "X4G") (pin "1") (pinfunction "1_1") (pintype "passive"))
      (node (ref "X4R") (pin "1") (pinfunction "1_1") (pintype "passive"))
      (node (ref "X5B") (pin "1") (pinfunction "1_1") (pintype "passive"))
      (node (ref "X5G") (pin "1") (pinfunction "1_1") (pintype "passive"))
      (node (ref "X5R") (pin "1") (pinfunction "1_1") (pintype "passive"))
      (node (ref "X6B") (pin "1") (pinfunction "1_1") (pintype "passive"))
      (node (ref "X6G") (pin "1") (pinfunction "1_1") (pintype "passive"))
      (node (ref "X6R") (pin "1") (pinfunction "1_1") (pintype "passive"))
      (node (ref "X7B") (pin "1") (pinfunction "1_1") (pintype "passive"))
      (node (ref "X7G") (pin "1") (pinfunction "1_1") (pintype "passive"))
      (node (ref "X7R") (pin "1") (pinfunction "1_1") (pintype "passive"))
      (node (ref "X8B") (pin "1") (pinfunction "1_1") (pintype "passive"))
      (node (ref "X8G") (pin "1") (pinfunction "1_1") (pintype "passive"))
      (node (ref "X8R") (pin "1") (pinfunction "1_1") (pintype "passive"))
      (node (ref "X9") (pin "1") (pinfunction "1_1") (pintype "passive"))
      (node (ref "X9") (pin "2") (pinfunction "2_2") (pintype "passive"))
      (node (ref "X9") (pin "3") (pinfunction "3_3") (pintype "passive"))
    )
  )
)
